# SCH_ESP32-Furnace-Controller_2026-05-20.net
KiCad netlist of a schematic drawn in EasyEDA
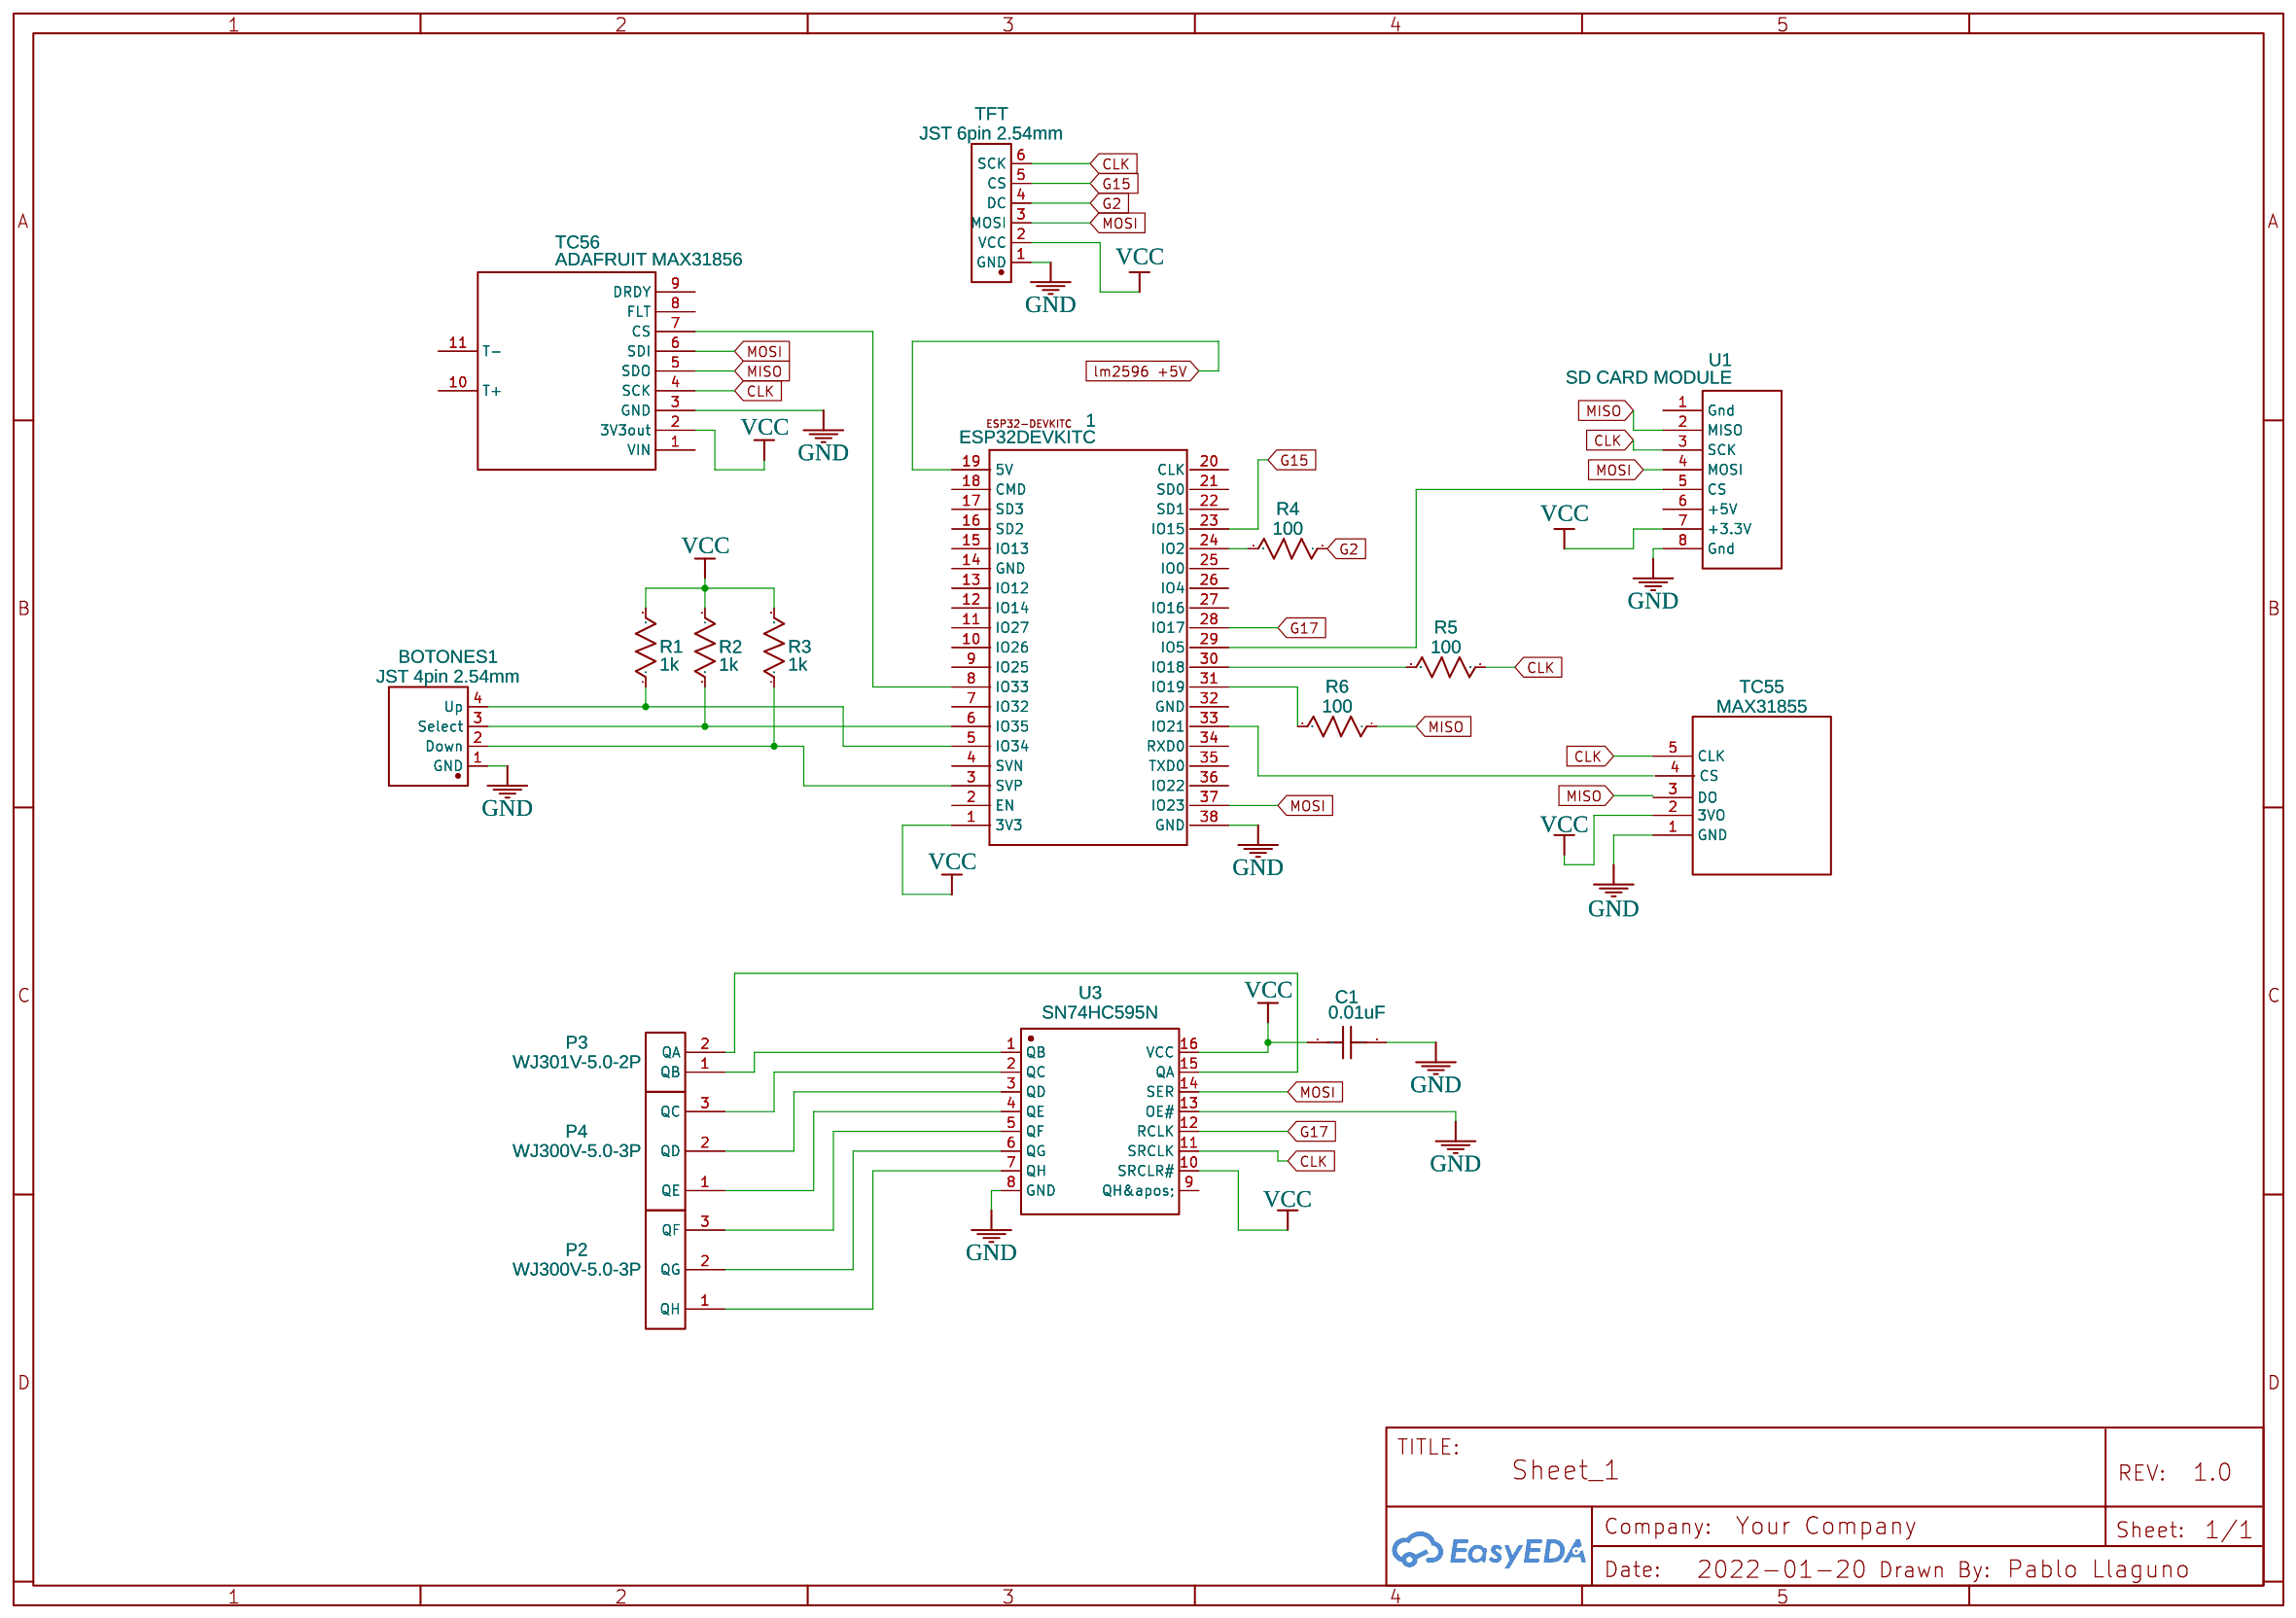
[diagram p0: Sheet_1]
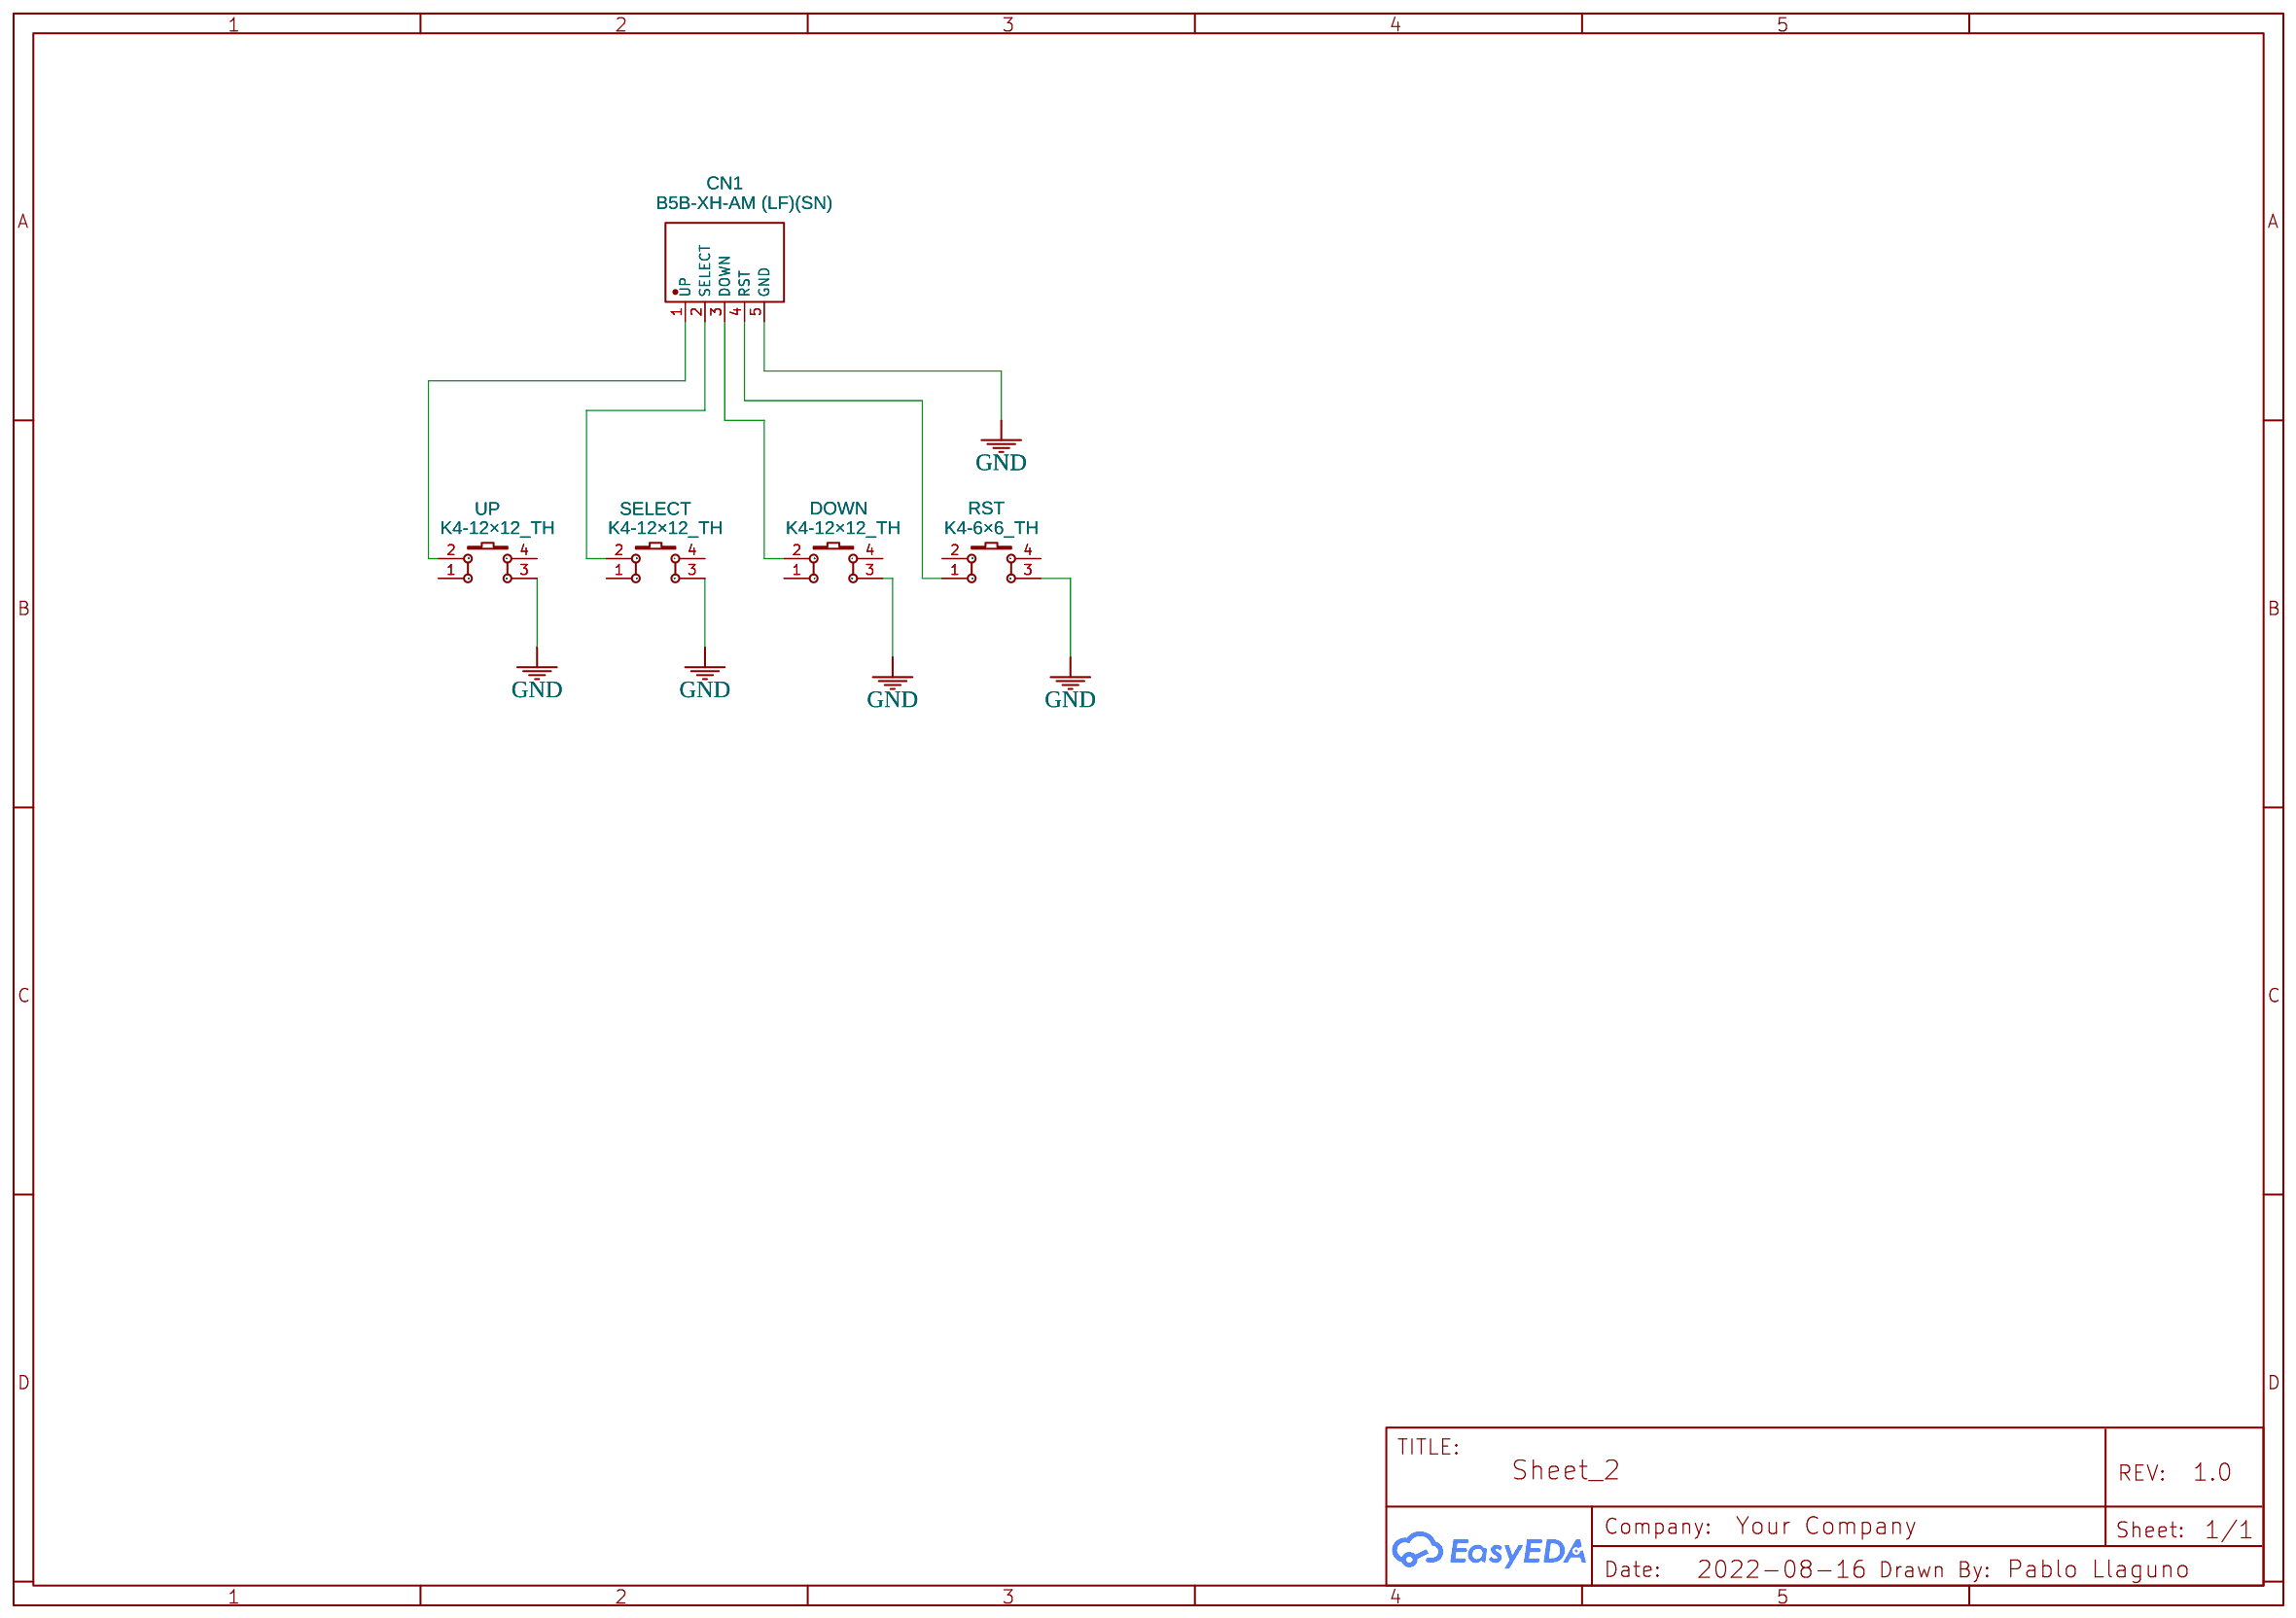
[diagram p1: Sheet_2]

(export (version "E")
  (design (tool "Eeschema 10.0.6"))
  (components
    (comp (ref "1") (value "ESP32DEVKITC") (libsource (lib "") (part "ESP32DEVKITC")))
    (comp (ref "BOTONES1")
      (value "JST 4pin 2.54mm")
      (fields (field (name "Manufacturer") "Boom Precision Elec"))
      (libsource (lib "") (part "XH-4AW M"))
    )
    (comp (ref "C1") (value "0.01uF") (libsource (lib "") (part "C_RAD-0.2_US")))
    (comp (ref "P2")
      (value "WJ300V-5.0-3P")
      (fields (field (name "Manufacturer") "ReliaPro"))
      (libsource (lib "") (part "WJ300V-5.0-3P"))
    )
    (comp (ref "P3")
      (value "WJ301V-5.0-2P")
      (fields (field (name "Manufacturer") "ReliaPro"))
      (libsource (lib "") (part "WJ301V-5.0-2P"))
    )
    (comp (ref "P4")
      (value "WJ300V-5.0-3P")
      (fields (field (name "Manufacturer") "ReliaPro"))
      (libsource (lib "") (part "WJ300V-5.0-3P_1"))
    )
    (comp (ref "R1") (value "1k") (libsource (lib "") (part "R_AXIAL-0.5_US")))
    (comp (ref "R2") (value "1k") (libsource (lib "") (part "R_AXIAL-0.5_US_2")))
    (comp (ref "R3") (value "1k") (libsource (lib "") (part "R_AXIAL-0.5_US")))
    (comp (ref "R4") (value "100") (libsource (lib "") (part "R_AXIAL-0.5_US_1")))
    (comp (ref "R5") (value "100") (libsource (lib "") (part "R_AXIAL-0.5_US_1")))
    (comp (ref "R6") (value "100") (libsource (lib "") (part "R_AXIAL-0.5_US_1")))
    (comp (ref "TC55") (value "MAX31855") (libsource (lib "") (part "MAX31855")))
    (comp (ref "TC56")
      (value "ADAFRUIT MAX31856")
      (fields (field (name "Manufacturer Part") "ADAFRUIT"))
      (libsource (lib "") (part "ADAFRUIT MAX31856"))
    )
    (comp (ref "TFT")
      (value "JST 6pin 2.54mm")
      (fields (field (name "Manufacturer Part") "XH-6AW") (field (name "Manufacturer") "HCTL(华灿天禄)"))
      (libsource (lib "") (part "XH-6AW_C2908615"))
    )
    (comp (ref "U1")
      (value "SD CARD MODULE")
      (fields (field (name "Manufacturer Part") "sd card module"))
      (libsource (lib "") (part "SD CARD MODULE"))
    )
    (comp (ref "U3")
      (value "SN74HC595N")
      (fields (field (name "Manufacturer") "TI"))
      (libsource (lib "") (part "SN74HC595N"))
    )
    (comp (ref "CN1")
      (value "B5B-XH-AM (LF)(SN)")
      (fields (field (name "Manufacturer") "JST Sales America"))
      (libsource (lib "") (part "B5B-XH-AM (LF)(SN)"))
    )
    (comp (ref "DOWN")
      (value "K4-12×12_TH")
      (fields (field (name "Manufacturer Part") "K2-1103DP-M4SW-04") (field (name "Manufacturer") "韩国韩荣"))
      (libsource (lib "") (part "K4-12×12_TH"))
    )
    (comp (ref "RST")
      (value "K4-6×6_TH")
      (fields (field (name "Manufacturer Part") "K2-1102DP-E4SW-04") (field (name "Manufacturer") "韩国韩荣"))
      (libsource (lib "") (part "K4-6×6_TH"))
    )
    (comp (ref "SELECT")
      (value "K4-12×12_TH")
      (fields (field (name "Manufacturer Part") "K2-1103DP-M4SW-04") (field (name "Manufacturer") "韩国韩荣"))
      (libsource (lib "") (part "K4-12×12_TH_2"))
    )
    (comp (ref "UP")
      (value "K4-12×12_TH")
      (fields (field (name "Manufacturer Part") "K2-1103DP-M4SW-04") (field (name "Manufacturer") "韩国韩荣"))
      (libsource (lib "") (part "K4-12×12_TH_1"))
    )
  )
  (nets
    (net (code "1") (name "CLK") (class "Default")
      (node (ref "R5") (pin "1") (pinfunction "1_1") (pintype "unspecified"))
      (node (ref "TC55") (pin "5") (pinfunction "CLK_5") (pintype "unspecified"))
      (node (ref "TC56") (pin "4") (pinfunction "SCK_4") (pintype "unspecified"))
      (node (ref "TFT") (pin "6") (pinfunction "SCK_6") (pintype "unspecified"))
      (node (ref "U1") (pin "3") (pinfunction "SCK_3") (pintype "unspecified"))
      (node (ref "U3") (pin "11") (pinfunction "SRCLK_11") (pintype "unspecified"))
    )
    (net (code "2") (name "G2") (class "Default")
      (node (ref "R4") (pin "1") (pinfunction "1_1") (pintype "unspecified"))
      (node (ref "TFT") (pin "4") (pinfunction "DC_4") (pintype "unspecified"))
    )
    (net (code "3") (name "G15") (class "Default")
      (node (ref "1") (pin "23") (pinfunction "IO15_23") (pintype "bidirectional"))
      (node (ref "TFT") (pin "5") (pinfunction "CS_5") (pintype "unspecified"))
    )
    (net (code "4") (name "G17") (class "Default")
      (node (ref "1") (pin "28") (pinfunction "IO17_28") (pintype "bidirectional"))
      (node (ref "U3") (pin "12") (pinfunction "RCLK_12") (pintype "unspecified"))
    )
    (net (code "5") (name "GND") (class "Default")
      (node (ref "1") (pin "38") (pinfunction "GND_38") (pintype "bidirectional"))
      (node (ref "BOTONES1") (pin "1") (pinfunction "GND_1") (pintype "unspecified"))
      (node (ref "C1") (pin "2") (pinfunction "2_2") (pintype "unspecified"))
      (node (ref "CN1") (pin "5") (pinfunction "GND_5") (pintype "unspecified"))
      (node (ref "DOWN") (pin "3") (pinfunction "3_3") (pintype "unspecified"))
      (node (ref "RST") (pin "3") (pinfunction "3_3") (pintype "unspecified"))
      (node (ref "SELECT") (pin "3") (pinfunction "3_3") (pintype "unspecified"))
      (node (ref "TC55") (pin "1") (pinfunction "GND_1") (pintype "unspecified"))
      (node (ref "TC56") (pin "3") (pinfunction "GND_3") (pintype "unspecified"))
      (node (ref "TFT") (pin "1") (pinfunction "GND_1") (pintype "unspecified"))
      (node (ref "U1") (pin "8") (pinfunction "Gnd_8") (pintype "unspecified"))
      (node (ref "U3") (pin "13") (pinfunction "OE#_13") (pintype "unspecified"))
      (node (ref "U3") (pin "8") (pinfunction "GND_8") (pintype "unspecified"))
      (node (ref "UP") (pin "3") (pinfunction "3_3") (pintype "unspecified"))
    )
    (net (code "6") (name "MISO") (class "Default")
      (node (ref "R6") (pin "1") (pinfunction "1_1") (pintype "unspecified"))
      (node (ref "TC56") (pin "5") (pinfunction "SDO_5") (pintype "unspecified"))
      (node (ref "U1") (pin "2") (pinfunction "MISO_2") (pintype "unspecified"))
    )
    (net (code "7") (name "MOSI") (class "Default")
      (node (ref "1") (pin "37") (pinfunction "IO23_37") (pintype "bidirectional"))
      (node (ref "TC56") (pin "6") (pinfunction "SDI_6") (pintype "unspecified"))
      (node (ref "TFT") (pin "3") (pinfunction "MOSI_3") (pintype "unspecified"))
      (node (ref "U1") (pin "4") (pinfunction "MOSI_4") (pintype "unspecified"))
      (node (ref "U3") (pin "14") (pinfunction "SER_14") (pintype "unspecified"))
    )
    (net (code "8") (name "Net-(1-IO2)") (class "Default")
      (node (ref "1") (pin "24") (pinfunction "IO2_24") (pintype "bidirectional"))
      (node (ref "R4") (pin "2") (pinfunction "2_2") (pintype "unspecified"))
    )
    (net (code "9") (name "Net-(1-IO5)") (class "Default")
      (node (ref "1") (pin "29") (pinfunction "IO5_29") (pintype "bidirectional"))
      (node (ref "U1") (pin "5") (pinfunction "CS_5") (pintype "unspecified"))
    )
    (net (code "10") (name "Net-(1-IO18)") (class "Default")
      (node (ref "1") (pin "30") (pinfunction "IO18_30") (pintype "bidirectional"))
      (node (ref "R5") (pin "2") (pinfunction "2_2") (pintype "unspecified"))
    )
    (net (code "11") (name "Net-(1-IO19)") (class "Default")
      (node (ref "1") (pin "31") (pinfunction "IO19_31") (pintype "bidirectional"))
      (node (ref "R6") (pin "2") (pinfunction "2_2") (pintype "unspecified"))
    )
    (net (code "12") (name "Net-(1-IO33)") (class "Default")
      (node (ref "1") (pin "8") (pinfunction "IO33_8") (pintype "bidirectional"))
      (node (ref "TC56") (pin "7") (pinfunction "CS_7") (pintype "unspecified"))
    )
    (net (code "13") (name "Net-(1-IO34)") (class "Default")
      (node (ref "1") (pin "5") (pinfunction "IO34_5") (pintype "bidirectional"))
      (node (ref "BOTONES1") (pin "4") (pinfunction "Up_4") (pintype "unspecified"))
      (node (ref "R1") (pin "1") (pinfunction "1_1") (pintype "unspecified"))
    )
    (net (code "14") (name "Net-(1-IO35)") (class "Default")
      (node (ref "1") (pin "6") (pinfunction "IO35_6") (pintype "bidirectional"))
      (node (ref "BOTONES1") (pin "3") (pinfunction "Select_3") (pintype "unspecified"))
      (node (ref "R2") (pin "2") (pinfunction "2_2") (pintype "unspecified"))
    )
    (net (code "15") (name "Net-(1-SVP)") (class "Default")
      (node (ref "1") (pin "3") (pinfunction "SVP_3") (pintype "bidirectional"))
      (node (ref "BOTONES1") (pin "2") (pinfunction "Down_2") (pintype "unspecified"))
      (node (ref "R3") (pin "1") (pinfunction "1_1") (pintype "unspecified"))
    )
    (net (code "16") (name "Net-(CN1-DOWN)") (class "Default")
      (node (ref "CN1") (pin "3") (pinfunction "DOWN_3") (pintype "unspecified"))
      (node (ref "DOWN") (pin "2") (pinfunction "2_2") (pintype "unspecified"))
    )
    (net (code "17") (name "Net-(CN1-RST)") (class "Default")
      (node (ref "CN1") (pin "4") (pinfunction "RST_4") (pintype "unspecified"))
      (node (ref "RST") (pin "1") (pinfunction "1_1") (pintype "unspecified"))
    )
    (net (code "18") (name "Net-(CN1-SELECT)") (class "Default")
      (node (ref "CN1") (pin "2") (pinfunction "SELECT_2") (pintype "unspecified"))
      (node (ref "SELECT") (pin "2") (pinfunction "2_2") (pintype "unspecified"))
    )
    (net (code "19") (name "Net-(CN1-UP)") (class "Default")
      (node (ref "CN1") (pin "1") (pinfunction "UP_1") (pintype "unspecified"))
      (node (ref "UP") (pin "2") (pinfunction "2_2") (pintype "unspecified"))
    )
    (net (code "20") (name "Net-(P2-QF)") (class "Default")
      (node (ref "P2") (pin "3") (pinfunction "QF_3") (pintype "unspecified"))
      (node (ref "U3") (pin "5") (pinfunction "QF_5") (pintype "unspecified"))
    )
    (net (code "21") (name "Net-(P2-QG)") (class "Default")
      (node (ref "P2") (pin "2") (pinfunction "QG_2") (pintype "unspecified"))
      (node (ref "U3") (pin "6") (pinfunction "QG_6") (pintype "unspecified"))
    )
    (net (code "22") (name "Net-(P2-QH)") (class "Default")
      (node (ref "P2") (pin "1") (pinfunction "QH_1") (pintype "unspecified"))
      (node (ref "U3") (pin "7") (pinfunction "QH_7") (pintype "unspecified"))
    )
    (net (code "23") (name "Net-(P3-QA)") (class "Default")
      (node (ref "P3") (pin "2") (pinfunction "QA_2") (pintype "unspecified"))
      (node (ref "U3") (pin "15") (pinfunction "QA_15") (pintype "unspecified"))
    )
    (net (code "24") (name "Net-(P3-QB)") (class "Default")
      (node (ref "P3") (pin "1") (pinfunction "QB_1") (pintype "unspecified"))
      (node (ref "U3") (pin "1") (pinfunction "QB_1") (pintype "unspecified"))
    )
    (net (code "25") (name "Net-(P4-QC)") (class "Default")
      (node (ref "P4") (pin "3") (pinfunction "QC_3") (pintype "unspecified"))
      (node (ref "U3") (pin "2") (pinfunction "QC_2") (pintype "unspecified"))
    )
    (net (code "26") (name "Net-(P4-QD)") (class "Default")
      (node (ref "P4") (pin "2") (pinfunction "QD_2") (pintype "unspecified"))
      (node (ref "U3") (pin "3") (pinfunction "QD_3") (pintype "unspecified"))
    )
    (net (code "27") (name "Net-(P4-QE)") (class "Default")
      (node (ref "P4") (pin "1") (pinfunction "QE_1") (pintype "unspecified"))
      (node (ref "U3") (pin "4") (pinfunction "QE_4") (pintype "unspecified"))
    )
    (net (code "28") (name "VCC") (class "Default")
      (node (ref "1") (pin "1") (pinfunction "3V3_1") (pintype "bidirectional"))
      (node (ref "C1") (pin "1") (pinfunction "1_1") (pintype "unspecified"))
      (node (ref "R1") (pin "2") (pinfunction "2_2") (pintype "unspecified"))
      (node (ref "R2") (pin "1") (pinfunction "1_1") (pintype "unspecified"))
      (node (ref "R3") (pin "2") (pinfunction "2_2") (pintype "unspecified"))
      (node (ref "TC55") (pin "2") (pinfunction "3VO_2") (pintype "unspecified"))
      (node (ref "TC56") (pin "2") (pinfunction "3V3out_2") (pintype "unspecified"))
      (node (ref "TFT") (pin "2") (pinfunction "VCC_2") (pintype "unspecified"))
      (node (ref "U1") (pin "7") (pinfunction "+3.3V_7") (pintype "unspecified"))
      (node (ref "U3") (pin "10") (pinfunction "SRCLR#_10") (pintype "unspecified"))
      (node (ref "U3") (pin "16") (pinfunction "VCC_16") (pintype "unspecified"))
    )
    (net (code "29") (name "lm2596 +5V") (class "Default")
      (node (ref "1") (pin "19") (pinfunction "5V_19") (pintype "bidirectional"))
    )
    (net (code "30") (name "unconnected-(1-CLK-Pad20)") (class "Default")
      (node (ref "1") (pin "20") (pinfunction "CLK_20") (pintype "bidirectional"))
    )
    (net (code "31") (name "unconnected-(1-CMD-Pad18)") (class "Default")
      (node (ref "1") (pin "18") (pinfunction "CMD_18") (pintype "bidirectional"))
    )
    (net (code "32") (name "unconnected-(1-EN-Pad2)") (class "Default")
      (node (ref "1") (pin "2") (pinfunction "EN_2") (pintype "bidirectional"))
    )
    (net (code "33") (name "unconnected-(1-GND-Pad14)") (class "Default")
      (node (ref "1") (pin "14") (pinfunction "GND_14") (pintype "bidirectional"))
    )
    (net (code "34") (name "unconnected-(1-GND-Pad32)") (class "Default")
      (node (ref "1") (pin "32") (pinfunction "GND_32") (pintype "bidirectional"))
    )
    (net (code "35") (name "unconnected-(1-IO0-Pad25)") (class "Default")
      (node (ref "1") (pin "25") (pinfunction "IO0_25") (pintype "bidirectional"))
    )
    (net (code "36") (name "unconnected-(1-IO4-Pad26)") (class "Default")
      (node (ref "1") (pin "26") (pinfunction "IO4_26") (pintype "bidirectional"))
    )
    (net (code "37") (name "unconnected-(1-IO12-Pad13)") (class "Default")
      (node (ref "1") (pin "13") (pinfunction "IO12_13") (pintype "bidirectional"))
    )
    (net (code "38") (name "unconnected-(1-IO13-Pad15)") (class "Default")
      (node (ref "1") (pin "15") (pinfunction "IO13_15") (pintype "bidirectional"))
    )
    (net (code "39") (name "unconnected-(1-IO14-Pad12)") (class "Default")
      (node (ref "1") (pin "12") (pinfunction "IO14_12") (pintype "bidirectional"))
    )
    (net (code "40") (name "unconnected-(1-IO16-Pad27)") (class "Default")
      (node (ref "1") (pin "27") (pinfunction "IO16_27") (pintype "bidirectional"))
    )
    (net (code "41") (name "unconnected-(1-IO21-Pad33)") (class "Default")
      (node (ref "1") (pin "33") (pinfunction "IO21_33") (pintype "bidirectional"))
    )
    (net (code "42") (name "unconnected-(1-IO22-Pad36)") (class "Default")
      (node (ref "1") (pin "36") (pinfunction "IO22_36") (pintype "bidirectional"))
    )
    (net (code "43") (name "unconnected-(1-IO25-Pad9)") (class "Default")
      (node (ref "1") (pin "9") (pinfunction "IO25_9") (pintype "bidirectional"))
    )
    (net (code "44") (name "unconnected-(1-IO26-Pad10)") (class "Default")
      (node (ref "1") (pin "10") (pinfunction "IO26_10") (pintype "bidirectional"))
    )
    (net (code "45") (name "unconnected-(1-IO27-Pad11)") (class "Default")
      (node (ref "1") (pin "11") (pinfunction "IO27_11") (pintype "bidirectional"))
    )
    (net (code "46") (name "unconnected-(1-IO32-Pad7)") (class "Default")
      (node (ref "1") (pin "7") (pinfunction "IO32_7") (pintype "bidirectional"))
    )
    (net (code "47") (name "unconnected-(1-RXD0-Pad34)") (class "Default")
      (node (ref "1") (pin "34") (pinfunction "RXD0_34") (pintype "bidirectional"))
    )
    (net (code "48") (name "unconnected-(1-SD0-Pad21)") (class "Default")
      (node (ref "1") (pin "21") (pinfunction "SD0_21") (pintype "bidirectional"))
    )
    (net (code "49") (name "unconnected-(1-SD1-Pad22)") (class "Default")
      (node (ref "1") (pin "22") (pinfunction "SD1_22") (pintype "bidirectional"))
    )
    (net (code "50") (name "unconnected-(1-SD2-Pad16)") (class "Default")
      (node (ref "1") (pin "16") (pinfunction "SD2_16") (pintype "bidirectional"))
    )
    (net (code "51") (name "unconnected-(1-SD3-Pad17)") (class "Default")
      (node (ref "1") (pin "17") (pinfunction "SD3_17") (pintype "bidirectional"))
    )
    (net (code "52") (name "unconnected-(1-SVN-Pad4)") (class "Default")
      (node (ref "1") (pin "4") (pinfunction "SVN_4") (pintype "bidirectional"))
    )
    (net (code "53") (name "unconnected-(1-TXD0-Pad35)") (class "Default")
      (node (ref "1") (pin "35") (pinfunction "TXD0_35") (pintype "bidirectional"))
    )
    (net (code "54") (name "unconnected-(DOWN-Pad1)") (class "Default")
      (node (ref "DOWN") (pin "1") (pinfunction "1_1") (pintype "unspecified"))
    )
    (net (code "55") (name "unconnected-(DOWN-Pad4)") (class "Default")
      (node (ref "DOWN") (pin "4") (pinfunction "4_4") (pintype "unspecified"))
    )
    (net (code "56") (name "unconnected-(RST-Pad2)") (class "Default")
      (node (ref "RST") (pin "2") (pinfunction "2_2") (pintype "unspecified"))
    )
    (net (code "57") (name "unconnected-(RST-Pad4)") (class "Default")
      (node (ref "RST") (pin "4") (pinfunction "4_4") (pintype "unspecified"))
    )
    (net (code "58") (name "unconnected-(SELECT-Pad1)") (class "Default")
      (node (ref "SELECT") (pin "1") (pinfunction "1_1") (pintype "unspecified"))
    )
    (net (code "59") (name "unconnected-(SELECT-Pad4)") (class "Default")
      (node (ref "SELECT") (pin "4") (pinfunction "4_4") (pintype "unspecified"))
    )
    (net (code "60") (name "unconnected-(TC55-CS-Pad4)") (class "Default")
      (node (ref "TC55") (pin "4") (pinfunction "CS_4") (pintype "unspecified"))
    )
    (net (code "61") (name "unconnected-(TC55-DO-Pad3)") (class "Default")
      (node (ref "TC55") (pin "3") (pinfunction "DO_3") (pintype "unspecified"))
    )
    (net (code "62") (name "unconnected-(TC56-DRDY-Pad9)") (class "Default")
      (node (ref "TC56") (pin "9") (pinfunction "DRDY_9") (pintype "unspecified"))
    )
    (net (code "63") (name "unconnected-(TC56-FLT-Pad8)") (class "Default")
      (node (ref "TC56") (pin "8") (pinfunction "FLT_8") (pintype "unspecified"))
    )
    (net (code "64") (name "unconnected-(TC56-T+-Pad10)") (class "Default")
      (node (ref "TC56") (pin "10") (pinfunction "T+_10") (pintype "unspecified"))
    )
    (net (code "65") (name "unconnected-(TC56-T--Pad11)") (class "Default")
      (node (ref "TC56") (pin "11") (pinfunction "T-_11") (pintype "unspecified"))
    )
    (net (code "66") (name "unconnected-(TC56-VIN-Pad1)") (class "Default")
      (node (ref "TC56") (pin "1") (pinfunction "VIN_1") (pintype "unspecified"))
    )
    (net (code "67") (name "unconnected-(U1-+5V-Pad6)") (class "Default")
      (node (ref "U1") (pin "6") (pinfunction "+5V_6") (pintype "unspecified"))
    )
    (net (code "68") (name "unconnected-(U1-Gnd-Pad1)") (class "Default")
      (node (ref "U1") (pin "1") (pinfunction "Gnd_1") (pintype "unspecified"))
    )
    (net (code "69") (name "unconnected-(U3-QH&apos;-Pad9)") (class "Default")
      (node (ref "U3") (pin "9") (pinfunction "QH&apos;_9") (pintype "unspecified"))
    )
    (net (code "70") (name "unconnected-(UP-Pad1)") (class "Default")
      (node (ref "UP") (pin "1") (pinfunction "1_1") (pintype "unspecified"))
    )
    (net (code "71") (name "unconnected-(UP-Pad4)") (class "Default")
      (node (ref "UP") (pin "4") (pinfunction "4_4") (pintype "unspecified"))
    )
  )
)
